# myBox.net
KiCad netlist of a schematic drawn in EAGLE
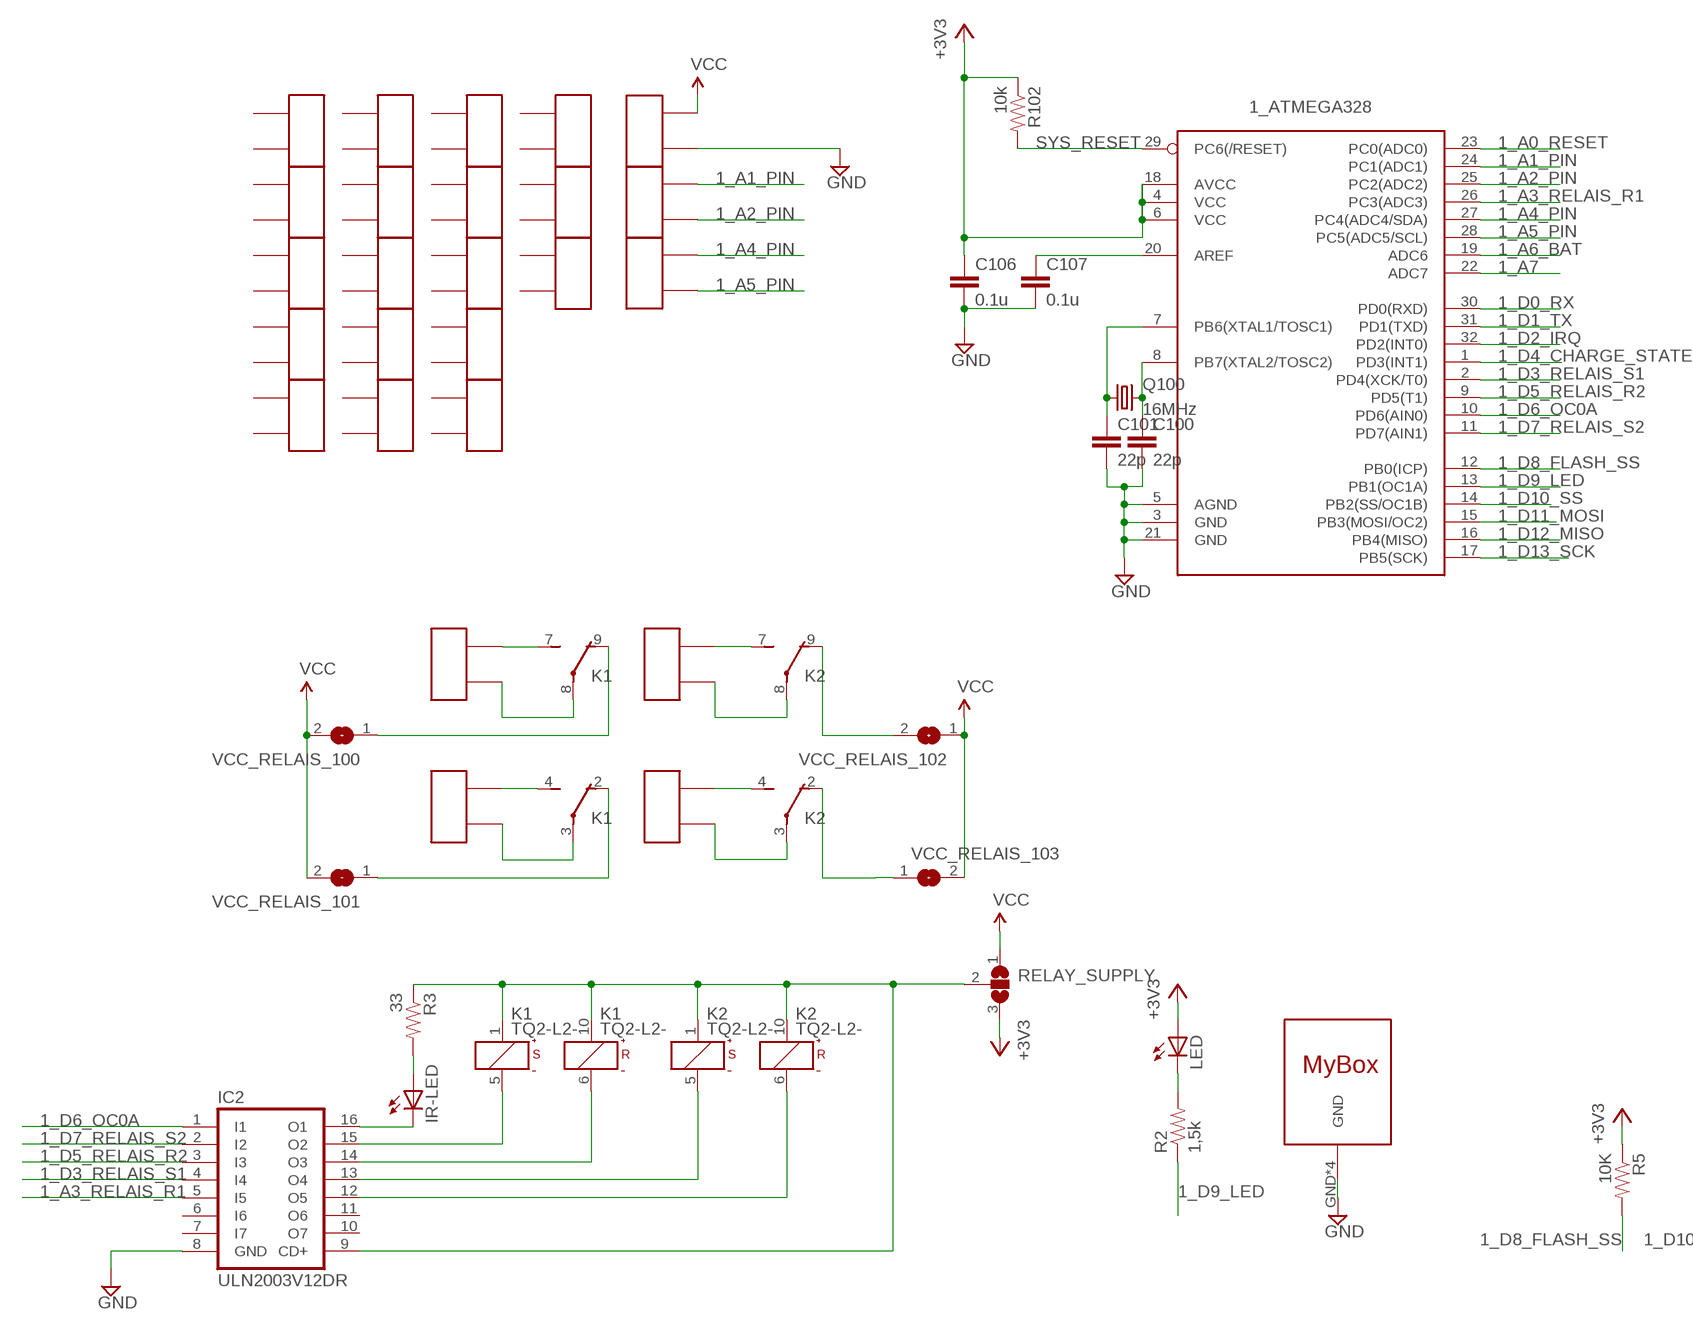
[diagram p0: schematic, sheet 1, part 1 of 2]
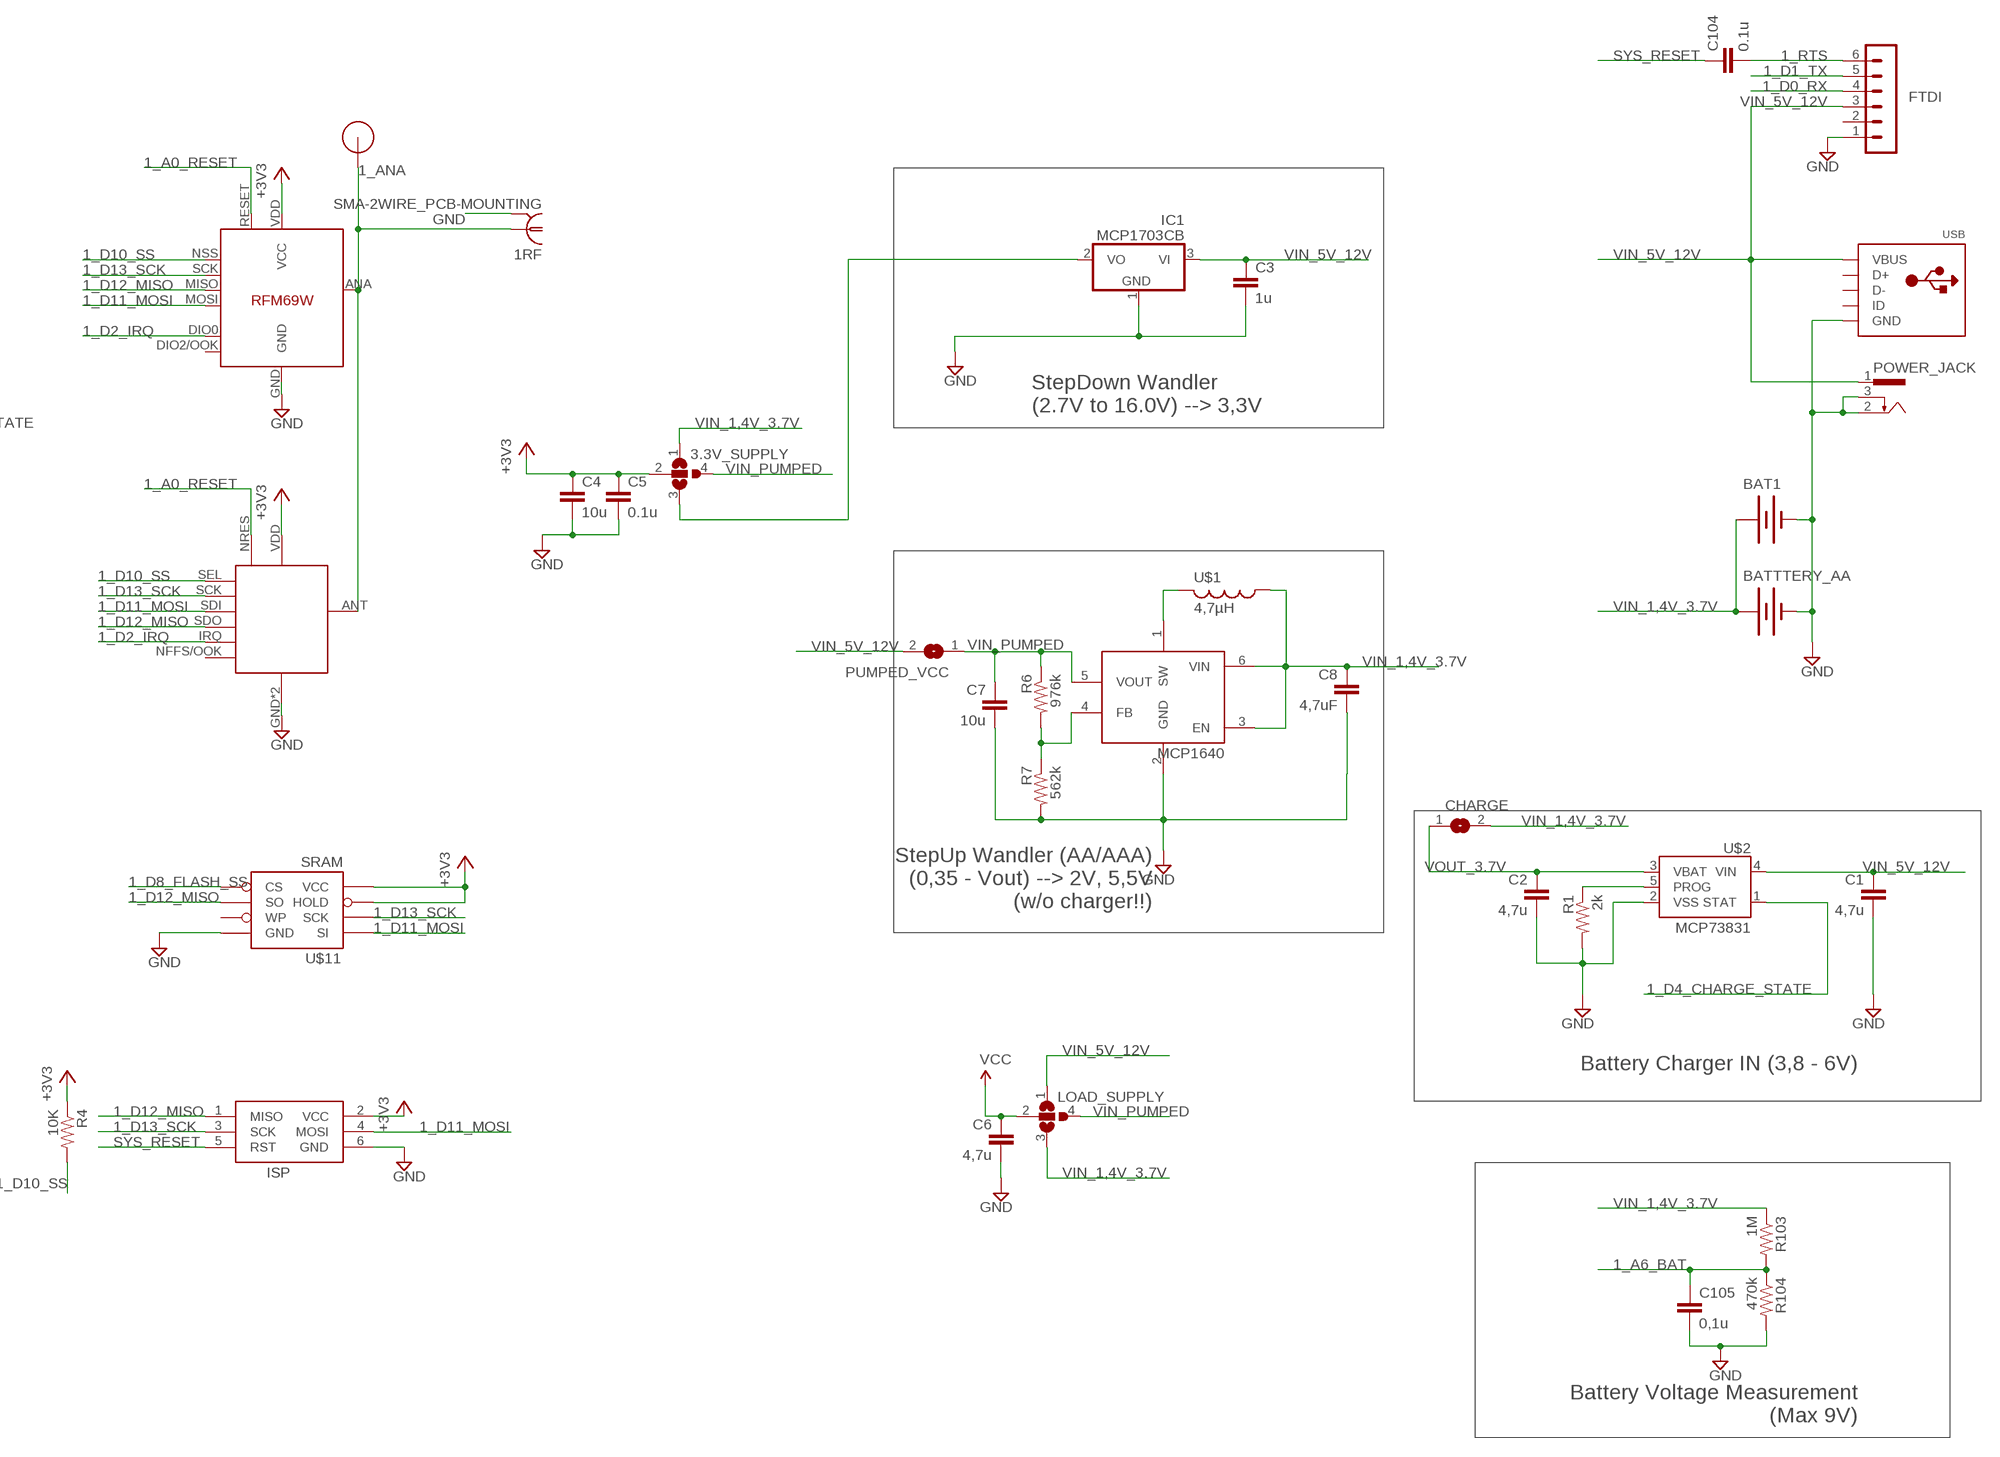
[diagram p1: schematic, sheet 1, part 2 of 2]

(export (version "E")
  (design (tool "Eeschema 10.0.6"))
  (components
    (comp (ref "1RF")
      (value "SMA-2WIRE_PCB-MOUNTING")
      (footprint "eagle-import:J01151A0931")
      (libsource (lib "eagle-import") (part "SMA-2WIRE_PCB-MOUNTING"))
    )
    (comp (ref "1_ATMEGA328")
      (value "ATMega-328")
      (footprint "eagle-import:TQFP32-08")
      (libsource (lib "eagle-import") (part "ATMEGA168/328TQFP32"))
    )
    (comp (ref "1_RFM12")
      (value "RFM12B_MINPADS")
      (footprint "eagle-import:RFM12B-MINPADS")
      (libsource (lib "eagle-import") (part "RFM12B_MINPADS"))
    )
    (comp (ref "1_RFM69")
      (value "RFM69_MINIPADS")
      (footprint "eagle-import:RFM69W-MINPADS")
      (libsource (lib "eagle-import") (part "RFM69_MINIPADS"))
    )
    (comp (ref "3.3V_SUPPLY")
      (value "SJ3W")
      (footprint "eagle-import:SJ_3")
      (libsource (lib "eagle-import") (part "SJ3W"))
    )
    (comp (ref "ADC1")
      (value "HDR_2PIN")
      (footprint "eagle-import:1X02_NS")
      (libsource (lib "eagle-import") (part "HDR_2PIN"))
    )
    (comp (ref "ADC2")
      (value "HDR_2PIN")
      (footprint "eagle-import:1X02_NS")
      (libsource (lib "eagle-import") (part "HDR_2PIN"))
    )
    (comp (ref "BAT1")
      (value "BATTERY")
      (footprint "eagle-import:BATTERY-CR2")
      (libsource (lib "eagle-import") (part "BATTERY"))
    )
    (comp (ref "BATTTERY_AA")
      (value "BATTERYAA")
      (footprint "eagle-import:BATTERY-AA")
      (libsource (lib "eagle-import") (part "BATTERYAA"))
    )
    (comp (ref "C1")
      (value "4,7u")
      (footprint "eagle-import:0603-CAP")
      (libsource (lib "eagle-import") (part "CAP0603-CAP"))
    )
    (comp (ref "C2")
      (value "4,7u")
      (footprint "eagle-import:0603-CAP")
      (libsource (lib "eagle-import") (part "CAP0603-CAP"))
    )
    (comp (ref "C3")
      (value "1u")
      (footprint "eagle-import:0603-CAP")
      (libsource (lib "eagle-import") (part "CAP0603-CAP"))
    )
    (comp (ref "C4")
      (value "10u")
      (footprint "eagle-import:0603-CAP")
      (libsource (lib "eagle-import") (part "CAP0603-CAP"))
    )
    (comp (ref "C5")
      (value "0.1u")
      (footprint "eagle-import:0603-CAP")
      (libsource (lib "eagle-import") (part "CAP0603-CAP"))
    )
    (comp (ref "C6")
      (value "4,7u")
      (footprint "eagle-import:0603-CAP")
      (libsource (lib "eagle-import") (part "CAP0603-CAP"))
    )
    (comp (ref "C7")
      (value "10u")
      (footprint "eagle-import:0603-CAP")
      (libsource (lib "eagle-import") (part "CAP0603-CAP"))
    )
    (comp (ref "C8")
      (value "4,7uF")
      (footprint "eagle-import:0603-CAP")
      (libsource (lib "eagle-import") (part "CAP0603-CAP"))
    )
    (comp (ref "C100")
      (value "22p")
      (footprint "eagle-import:0603-CAP")
      (libsource (lib "eagle-import") (part "CAP0603-CAP"))
    )
    (comp (ref "C101")
      (value "22p")
      (footprint "eagle-import:0603-CAP")
      (libsource (lib "eagle-import") (part "CAP0603-CAP"))
    )
    (comp (ref "C104")
      (value "0.1u")
      (footprint "eagle-import:0603-CAP")
      (libsource (lib "eagle-import") (part "CAP0603-CAP"))
    )
    (comp (ref "C105")
      (value "0,1u")
      (footprint "eagle-import:0603-CAP")
      (libsource (lib "eagle-import") (part "CAP0603-CAP"))
    )
    (comp (ref "C106")
      (value "0.1u")
      (footprint "eagle-import:0603-CAP")
      (libsource (lib "eagle-import") (part "CAP0603-CAP"))
    )
    (comp (ref "C107")
      (value "0.1u")
      (footprint "eagle-import:0603-CAP")
      (libsource (lib "eagle-import") (part "CAP0603-CAP"))
    )
    (comp (ref "CHARGE")
      (value "SJ")
      (footprint "eagle-import:SJ")
      (libsource (lib "eagle-import") (part "SJ"))
    )
    (comp (ref "FTDI")
      (value "FTDI")
      (footprint "eagle-import:MA06-1")
      (libsource (lib "eagle-import") (part "MA06-1"))
    )
    (comp (ref "IC1")
      (value "MCP1703CB")
      (footprint "eagle-import:SOT23")
      (libsource (lib "eagle-import") (part "MCP1703CB"))
    )
    (comp (ref "IC2")
      (value "ULN2003V12DR")
      (footprint "eagle-import:SO16")
      (libsource (lib "eagle-import") (part "ULN2003AD"))
    )
    (comp (ref "IR-LED")
      (value "LED5MM")
      (footprint "eagle-import:LED5MM")
      (libsource (lib "eagle-import") (part "led_LED5MM"))
    )
    (comp (ref "IR/RELAY_SATELLITE")
      (value "MY-BOX")
      (footprint "eagle-import:MY-BOX")
      (libsource (lib "eagle-import") (part "MY-BOX"))
    )
    (comp (ref "ISP")
      (value "AVRISP")
      (footprint "eagle-import:AVRISP-EDGE")
      (fields (field (name "BUERKLIN") "56F6228"))
      (libsource (lib "eagle-import") (part "AVRISP"))
    )
    (comp (ref "K1")
      (value "TQ2-L2-")
      (footprint "eagle-import:TQ2")
      (fields
        (field (name "MF") "AROMAT/ MATSUSHITA")
        (field (name "MPN") "TQ2-L2-9V")
        (field (name "BUERKLIN") "30 G 7570")
        (field (name "MPN_1") "TQ2-L2-3V")
      )
      (libsource (lib "eagle-import") (part "TQ2?-L2-"))
    )
    (comp (ref "K2")
      (value "TQ2-L2-")
      (footprint "eagle-import:TQ2")
      (fields
        (field (name "MF") "AROMAT/ MATSUSHITA")
        (field (name "MPN") "TQ2-L2-9V")
        (field (name "BUERKLIN") "30 G 7570")
        (field (name "MPN_1") "TQ2-L2-3V")
      )
      (libsource (lib "eagle-import") (part "TQ2?-L2-"))
    )
    (comp (ref "LED")
      (value "LED3MM")
      (footprint "eagle-import:LED3MM")
      (libsource (lib "eagle-import") (part "LED3MM"))
    )
    (comp (ref "LOAD_SUPPLY")
      (value "SJ3W")
      (footprint "eagle-import:SJ_3")
      (libsource (lib "eagle-import") (part "SJ3W"))
    )
    (comp (ref "POWER_JACK")
      (value "LUMBERG_1613-200-62")
      (footprint "eagle-import:733980-62")
      (libsource (lib "eagle-import") (part "LUMBERG_1613-200-62"))
    )
    (comp (ref "PUMPED_VCC")
      (value "SJ")
      (footprint "eagle-import:SJ")
      (libsource (lib "eagle-import") (part "SJ"))
    )
    (comp (ref "Q100")
      (value "16MHz")
      (footprint "eagle-import:HC49_S")
      (libsource (lib "eagle-import") (part "CRYSTALHC49S"))
    )
    (comp (ref "R1")
      (value "2k")
      (footprint "eagle-import:0603-RES")
      (libsource (lib "eagle-import") (part "RESISTOR0603-RES"))
    )
    (comp (ref "R2")
      (value "1,5k")
      (footprint "eagle-import:0603-RES")
      (libsource (lib "eagle-import") (part "RESISTOR0603-RES"))
    )
    (comp (ref "R3")
      (value "33")
      (footprint "eagle-import:0603-RES")
      (libsource (lib "eagle-import") (part "RESISTOR0603-RES"))
    )
    (comp (ref "R4")
      (value "10K")
      (footprint "eagle-import:0603-RES")
      (libsource (lib "eagle-import") (part "RESISTOR0603-RES"))
    )
    (comp (ref "R5")
      (value "10K")
      (footprint "eagle-import:0603-RES")
      (libsource (lib "eagle-import") (part "RESISTOR0603-RES"))
    )
    (comp (ref "R6")
      (value "976k")
      (footprint "eagle-import:0603-RES")
      (libsource (lib "eagle-import") (part "RESISTOR0603-RES"))
    )
    (comp (ref "R7")
      (value "562k")
      (footprint "eagle-import:0603-RES")
      (libsource (lib "eagle-import") (part "RESISTOR0603-RES"))
    )
    (comp (ref "R102")
      (value "10k")
      (footprint "eagle-import:0603-RES")
      (libsource (lib "eagle-import") (part "RESISTOR0603-RES"))
    )
    (comp (ref "R103")
      (value "1M")
      (footprint "eagle-import:0603-RES")
      (libsource (lib "eagle-import") (part "RESISTOR0603-RES"))
    )
    (comp (ref "R104")
      (value "470k")
      (footprint "eagle-import:0603-RES")
      (libsource (lib "eagle-import") (part "RESISTOR0603-RES"))
    )
    (comp (ref "RELAY_SUPPLY")
      (value "SJ2W")
      (footprint "eagle-import:SJ_2")
      (libsource (lib "eagle-import") (part "SJ2W"))
    )
    (comp (ref "U$1")
      (value "4,7µH")
      (footprint "eagle-import:INDUCTOR_EPCOS")
      (libsource (lib "eagle-import") (part "INDUCTOR_B82462G"))
    )
    (comp (ref "U$2")
      (value "MCP73831")
      (footprint "eagle-import:SOT23-5")
      (libsource (lib "eagle-import") (part "MCP73831"))
    )
    (comp (ref "U$3")
      (value "HDR_2PIN")
      (footprint "eagle-import:1X02_NS")
      (libsource (lib "eagle-import") (part "HDR_2PIN"))
    )
    (comp (ref "U$4")
      (value "HDR_2PIN")
      (footprint "eagle-import:1X02_NS")
      (libsource (lib "eagle-import") (part "HDR_2PIN"))
    )
    (comp (ref "U$5")
      (value "HDR_2PIN")
      (footprint "eagle-import:1X02_NS")
      (libsource (lib "eagle-import") (part "HDR_2PIN"))
    )
    (comp (ref "U$6")
      (value "HDR_2PIN")
      (footprint "eagle-import:1X02_NS")
      (libsource (lib "eagle-import") (part "HDR_2PIN"))
    )
    (comp (ref "U$7")
      (value "HDR_2PIN")
      (footprint "eagle-import:1X02_NS")
      (libsource (lib "eagle-import") (part "HDR_2PIN"))
    )
    (comp (ref "U$8")
      (value "HDR_2PIN")
      (footprint "eagle-import:1X02_NS")
      (libsource (lib "eagle-import") (part "HDR_2PIN"))
    )
    (comp (ref "U$9")
      (value "HDR_2PIN")
      (footprint "eagle-import:1X02_NS")
      (libsource (lib "eagle-import") (part "HDR_2PIN"))
    )
    (comp (ref "U$10")
      (value "HDR_2PIN")
      (footprint "eagle-import:1X02_NS")
      (libsource (lib "eagle-import") (part "HDR_2PIN"))
    )
    (comp (ref "U$11")
      (value "SRAM")
      (footprint "eagle-import:LOWPOWERLAB_SO08")
      (libsource (lib "eagle-import") (part "SRAM_32K256JEDEC_3.9MM"))
    )
    (comp (ref "U$12")
      (value "HDR_2PIN")
      (footprint "eagle-import:1X02_NS")
      (libsource (lib "eagle-import") (part "HDR_2PIN"))
    )
    (comp (ref "U$13")
      (value "HDR_2PIN")
      (footprint "eagle-import:1X02_NS")
      (libsource (lib "eagle-import") (part "HDR_2PIN"))
    )
    (comp (ref "U$14")
      (value "HDR_2PIN")
      (footprint "eagle-import:1X02_NS")
      (libsource (lib "eagle-import") (part "HDR_2PIN"))
    )
    (comp (ref "U$15")
      (value "HDR_2PIN")
      (footprint "eagle-import:1X02_NS")
      (libsource (lib "eagle-import") (part "HDR_2PIN"))
    )
    (comp (ref "U$16")
      (value "HDR_2PIN")
      (footprint "eagle-import:1X02_NS")
      (libsource (lib "eagle-import") (part "HDR_2PIN"))
    )
    (comp (ref "U$17")
      (value "HDR_2PIN")
      (footprint "eagle-import:1X02_NS")
      (libsource (lib "eagle-import") (part "HDR_2PIN"))
    )
    (comp (ref "U$18")
      (value "RFM12B_ANTENNA")
      (footprint "eagle-import:RFM12B-ANTENNA")
      (libsource (lib "eagle-import") (part "RFM12B_ANTENNA"))
    )
    (comp (ref "U$19")
      (value "HDR_2PIN")
      (footprint "eagle-import:1X02_NS")
      (libsource (lib "eagle-import") (part "HDR_2PIN"))
    )
    (comp (ref "U$20")
      (value "HDR_2PIN")
      (footprint "eagle-import:1X02_NS")
      (libsource (lib "eagle-import") (part "HDR_2PIN"))
    )
    (comp (ref "U$21")
      (value "HDR_2PIN")
      (footprint "eagle-import:1X02_NS")
      (libsource (lib "eagle-import") (part "HDR_2PIN"))
    )
    (comp (ref "U$22")
      (value "HDR_2PIN")
      (footprint "eagle-import:1X02_NS")
      (libsource (lib "eagle-import") (part "HDR_2PIN"))
    )
    (comp (ref "U$23")
      (value "HDR_2PIN")
      (footprint "eagle-import:1X02_NS")
      (libsource (lib "eagle-import") (part "HDR_2PIN"))
    )
    (comp (ref "U$24")
      (value "HDR_2PIN")
      (footprint "eagle-import:1X02_NS")
      (libsource (lib "eagle-import") (part "HDR_2PIN"))
    )
    (comp (ref "U$25")
      (value "HDR_2PIN")
      (footprint "eagle-import:1X02_NS")
      (libsource (lib "eagle-import") (part "HDR_2PIN"))
    )
    (comp (ref "U$26")
      (value "HDR_2PIN")
      (footprint "eagle-import:1X02_NS")
      (libsource (lib "eagle-import") (part "HDR_2PIN"))
    )
    (comp (ref "U1")
      (value "MCP1640")
      (footprint "eagle-import:SOT23-6")
      (libsource (lib "eagle-import") (part "MCP1640"))
    )
    (comp (ref "USB")
      (value "USBMINIB")
      (footprint "eagle-import:USB-MINIB")
      (libsource (lib "eagle-import") (part "USBMINIB"))
    )
    (comp (ref "VCC")
      (value "HDR_2PIN")
      (footprint "eagle-import:1X02_NS")
      (libsource (lib "eagle-import") (part "HDR_2PIN"))
    )
    (comp (ref "VCC_RELAIS_100")
      (value "SJ")
      (footprint "eagle-import:SJ")
      (libsource (lib "eagle-import") (part "SJ"))
    )
    (comp (ref "VCC_RELAIS_101")
      (value "SJ")
      (footprint "eagle-import:SJ")
      (libsource (lib "eagle-import") (part "SJ"))
    )
    (comp (ref "VCC_RELAIS_102")
      (value "SJ")
      (footprint "eagle-import:SJ")
      (libsource (lib "eagle-import") (part "SJ"))
    )
    (comp (ref "VCC_RELAIS_103")
      (value "SJ")
      (footprint "eagle-import:SJ")
      (libsource (lib "eagle-import") (part "SJ"))
    )
  )
  (nets
    (net (code "1") (name "+3V3") (class "Default")
      (node (ref "1_ATMEGA328") (pin "18") (pinfunction "AVCC_18") (pintype "bidirectional"))
      (node (ref "1_ATMEGA328") (pin "4") (pinfunction "VCC_4") (pintype "bidirectional"))
      (node (ref "1_ATMEGA328") (pin "6") (pinfunction "VCC_6") (pintype "bidirectional"))
      (node (ref "1_RFM12") (pin "VDD") (pinfunction "VDD_VDD") (pintype "bidirectional"))
      (node (ref "1_RFM69") (pin "VDD") (pinfunction "VCC_VDD") (pintype "power_in"))
      (node (ref "3.3V_SUPPLY") (pin "2") (pinfunction "2_2") (pintype "passive"))
      (node (ref "C106") (pin "1") (pinfunction "1_1") (pintype "passive"))
      (node (ref "C4") (pin "1") (pinfunction "1_1") (pintype "passive"))
      (node (ref "C5") (pin "1") (pinfunction "1_1") (pintype "passive"))
      (node (ref "ISP") (pin "2") (pinfunction "VCC_2") (pintype "power_in"))
      (node (ref "LED") (pin "A") (pinfunction "A_A") (pintype "passive"))
      (node (ref "R102") (pin "1") (pinfunction "1_1") (pintype "passive"))
      (node (ref "R4") (pin "1") (pinfunction "1_1") (pintype "passive"))
      (node (ref "R5") (pin "1") (pinfunction "1_1") (pintype "passive"))
      (node (ref "RELAY_SUPPLY") (pin "3") (pinfunction "3_3") (pintype "passive"))
      (node (ref "U$11") (pin "7_HOLD") (pinfunction "HOLD_7_HOLD") (pintype "bidirectional"))
      (node (ref "U$11") (pin "8_VCC") (pinfunction "VCC_8_VCC") (pintype "bidirectional"))
    )
    (net (code "2") (name "/1_A0_RESET") (class "Default")
      (node (ref "1_ATMEGA328") (pin "23") (pinfunction "PC0(ADC0)_23") (pintype "bidirectional"))
      (node (ref "1_RFM12") (pin "NRES") (pinfunction "NRES_NRES") (pintype "bidirectional"))
      (node (ref "1_RFM69") (pin "RESET") (pinfunction "RESET_RESET") (pintype "input"))
    )
    (net (code "3") (name "/1_A1_PIN") (class "Default")
      (node (ref "1_ATMEGA328") (pin "24") (pinfunction "PC1(ADC1)_24") (pintype "bidirectional"))
      (node (ref "ADC1") (pin "1") (pinfunction "P$1_1") (pintype "bidirectional"))
    )
    (net (code "4") (name "/1_A2_PIN") (class "Default")
      (node (ref "1_ATMEGA328") (pin "25") (pinfunction "PC2(ADC2)_25") (pintype "bidirectional"))
      (node (ref "ADC1") (pin "2") (pinfunction "P$2_2") (pintype "bidirectional"))
    )
    (net (code "5") (name "/1_A3_RELAIS_R1") (class "Default")
      (node (ref "1_ATMEGA328") (pin "26") (pinfunction "PC3(ADC3)_26") (pintype "bidirectional"))
      (node (ref "IC2") (pin "5") (pinfunction "I5_5") (pintype "input"))
    )
    (net (code "6") (name "/1_A4_PIN") (class "Default")
      (node (ref "1_ATMEGA328") (pin "27") (pinfunction "PC4(ADC4/SDA)_27") (pintype "bidirectional"))
      (node (ref "ADC2") (pin "1") (pinfunction "P$1_1") (pintype "bidirectional"))
    )
    (net (code "7") (name "/1_A5_PIN") (class "Default")
      (node (ref "1_ATMEGA328") (pin "28") (pinfunction "PC5(ADC5/SCL)_28") (pintype "bidirectional"))
      (node (ref "ADC2") (pin "2") (pinfunction "P$2_2") (pintype "bidirectional"))
    )
    (net (code "8") (name "/1_A6_BAT") (class "Default")
      (node (ref "1_ATMEGA328") (pin "19") (pinfunction "ADC6_19") (pintype "bidirectional"))
      (node (ref "C105") (pin "1") (pinfunction "1_1") (pintype "passive"))
      (node (ref "R103") (pin "2") (pinfunction "2_2") (pintype "passive"))
      (node (ref "R104") (pin "1") (pinfunction "1_1") (pintype "passive"))
    )
    (net (code "9") (name "/1_A7") (class "Default")
      (node (ref "1_ATMEGA328") (pin "22") (pinfunction "ADC7_22") (pintype "bidirectional"))
    )
    (net (code "10") (name "/1_ANA") (class "Default")
      (node (ref "1RF") (pin "1") (pinfunction "1_1") (pintype "passive"))
      (node (ref "1_RFM12") (pin "ANT") (pinfunction "ANT_ANT") (pintype "bidirectional"))
      (node (ref "1_RFM69") (pin "ANA") (pinfunction "ANT_ANA") (pintype "passive"))
      (node (ref "U$18") (pin "P$1") (pinfunction "1_P$1") (pintype "bidirectional"))
    )
    (net (code "11") (name "/1_D0_RX") (class "Default")
      (node (ref "1_ATMEGA328") (pin "30") (pinfunction "PD0(RXD)_30") (pintype "bidirectional"))
      (node (ref "FTDI") (pin "4") (pinfunction "4_4") (pintype "passive"))
    )
    (net (code "12") (name "/1_D1_TX") (class "Default")
      (node (ref "1_ATMEGA328") (pin "31") (pinfunction "PD1(TXD)_31") (pintype "bidirectional"))
      (node (ref "FTDI") (pin "5") (pinfunction "5_5") (pintype "passive"))
    )
    (net (code "13") (name "/1_D2_IRQ") (class "Default")
      (node (ref "1_ATMEGA328") (pin "32") (pinfunction "PD2(INT0)_32") (pintype "bidirectional"))
      (node (ref "1_RFM12") (pin "IRQ") (pinfunction "IRQ_IRQ") (pintype "bidirectional"))
      (node (ref "1_RFM69") (pin "DIO0") (pinfunction "DIO0/IRQ_DIO0") (pintype "open_collector"))
    )
    (net (code "14") (name "/1_D3_RELAIS_S1") (class "Default")
      (node (ref "1_ATMEGA328") (pin "2") (pinfunction "PD4(XCK/T0)_2") (pintype "bidirectional"))
      (node (ref "IC2") (pin "4") (pinfunction "I4_4") (pintype "input"))
    )
    (net (code "15") (name "/1_D4_CHARGE_STATE") (class "Default")
      (node (ref "1_ATMEGA328") (pin "1") (pinfunction "PD3(INT1)_1") (pintype "bidirectional"))
      (node (ref "U$2") (pin "1") (pinfunction "STAT_1") (pintype "output"))
    )
    (net (code "16") (name "/1_D5_RELAIS_R2") (class "Default")
      (node (ref "1_ATMEGA328") (pin "9") (pinfunction "PD5(T1)_9") (pintype "bidirectional"))
      (node (ref "IC2") (pin "3") (pinfunction "I3_3") (pintype "input"))
    )
    (net (code "17") (name "/1_D6_OC0A") (class "Default")
      (node (ref "1_ATMEGA328") (pin "10") (pinfunction "PD6(AIN0)_10") (pintype "bidirectional"))
      (node (ref "IC2") (pin "1") (pinfunction "I1_1") (pintype "input"))
    )
    (net (code "18") (name "/1_D7_RELAIS_S2") (class "Default")
      (node (ref "1_ATMEGA328") (pin "11") (pinfunction "PD7(AIN1)_11") (pintype "bidirectional"))
      (node (ref "IC2") (pin "2") (pinfunction "I2_2") (pintype "input"))
    )
    (net (code "19") (name "/1_D8_FLASH_SS") (class "Default")
      (node (ref "1_ATMEGA328") (pin "12") (pinfunction "PB0(ICP)_12") (pintype "bidirectional"))
      (node (ref "R5") (pin "2") (pinfunction "2_2") (pintype "passive"))
      (node (ref "U$11") (pin "1_CS") (pinfunction "CS_1_CS") (pintype "bidirectional"))
    )
    (net (code "20") (name "/1_D9_LED") (class "Default")
      (node (ref "1_ATMEGA328") (pin "13") (pinfunction "PB1(OC1A)_13") (pintype "bidirectional"))
      (node (ref "R2") (pin "1") (pinfunction "1_1") (pintype "passive"))
    )
    (net (code "21") (name "/1_D10_SS") (class "Default")
      (node (ref "1_ATMEGA328") (pin "14") (pinfunction "PB2(SS/OC1B)_14") (pintype "bidirectional"))
      (node (ref "1_RFM12") (pin "SEL") (pinfunction "SEL_SEL") (pintype "bidirectional"))
      (node (ref "1_RFM69") (pin "NSS") (pinfunction "SEL_NSS") (pintype "input"))
      (node (ref "R4") (pin "2") (pinfunction "2_2") (pintype "passive"))
    )
    (net (code "22") (name "/1_D11_MOSI") (class "Default")
      (node (ref "1_ATMEGA328") (pin "15") (pinfunction "PB3(MOSI/OC2)_15") (pintype "bidirectional"))
      (node (ref "1_RFM12") (pin "SDI") (pinfunction "SDI/MOSI_SDI") (pintype "bidirectional"))
      (node (ref "1_RFM69") (pin "MOSI") (pinfunction "MOSI_MOSI") (pintype "output"))
      (node (ref "ISP") (pin "4") (pinfunction "MOSI_4") (pintype "output"))
      (node (ref "U$11") (pin "5_SI") (pinfunction "SI_5_SI") (pintype "bidirectional"))
    )
    (net (code "23") (name "/1_D12_MISO") (class "Default")
      (node (ref "1_ATMEGA328") (pin "16") (pinfunction "PB4(MISO)_16") (pintype "bidirectional"))
      (node (ref "1_RFM12") (pin "SDO") (pinfunction "SDO/MISO_SDO") (pintype "bidirectional"))
      (node (ref "1_RFM69") (pin "MISO") (pinfunction "MISO_MISO") (pintype "input"))
      (node (ref "ISP") (pin "1") (pinfunction "MISO_1") (pintype "input"))
      (node (ref "U$11") (pin "2_SO") (pinfunction "SO_2_SO") (pintype "bidirectional"))
    )
    (net (code "24") (name "/1_D13_SCK") (class "Default")
      (node (ref "1_ATMEGA328") (pin "17") (pinfunction "PB5(SCK)_17") (pintype "bidirectional"))
      (node (ref "1_RFM12") (pin "SCK") (pinfunction "SCK_SCK") (pintype "bidirectional"))
      (node (ref "1_RFM69") (pin "SCK") (pinfunction "SCK_SCK") (pintype "input"))
      (node (ref "ISP") (pin "3") (pinfunction "SCK_3") (pintype "output"))
      (node (ref "U$11") (pin "6_SCK") (pinfunction "SCK_6_SCK") (pintype "bidirectional"))
    )
    (net (code "25") (name "/1_RTS") (class "Default")
      (node (ref "C104") (pin "2") (pinfunction "2_2") (pintype "passive"))
      (node (ref "FTDI") (pin "6") (pinfunction "6_6") (pintype "passive"))
    )
    (net (code "26") (name "/SYS_RESET") (class "Default")
      (node (ref "1_ATMEGA328") (pin "29") (pinfunction "PC6(/RESET)_29") (pintype "bidirectional"))
      (node (ref "C104") (pin "1") (pinfunction "1_1") (pintype "passive"))
      (node (ref "ISP") (pin "5") (pinfunction "RST_5") (pintype "output"))
      (node (ref "R102") (pin "2") (pinfunction "2_2") (pintype "passive"))
    )
    (net (code "27") (name "/VIN_1,4V_3.7V") (class "Default")
      (node (ref "3.3V_SUPPLY") (pin "1") (pinfunction "1_1") (pintype "passive"))
      (node (ref "BAT1") (pin "PWR@1") (pinfunction "+_PWR@1") (pintype "power_in"))
      (node (ref "BATTTERY_AA") (pin "PWR@1") (pinfunction "+_PWR@1") (pintype "power_in"))
      (node (ref "C8") (pin "1") (pinfunction "1_1") (pintype "passive"))
      (node (ref "CHARGE") (pin "2") (pinfunction "2_2") (pintype "passive"))
      (node (ref "LOAD_SUPPLY") (pin "3") (pinfunction "3_3") (pintype "passive"))
      (node (ref "R103") (pin "1") (pinfunction "1_1") (pintype "passive"))
      (node (ref "U$1") (pin "P$1") (pinfunction "1_P$1") (pintype "passive"))
      (node (ref "U1") (pin "3") (pinfunction "EN_3") (pintype "input"))
      (node (ref "U1") (pin "6") (pinfunction "VIN_6") (pintype "input"))
    )
    (net (code "28") (name "/VIN_5V_12V") (class "Default")
      (node (ref "C1") (pin "1") (pinfunction "1_1") (pintype "passive"))
      (node (ref "C3") (pin "1") (pinfunction "1_1") (pintype "passive"))
      (node (ref "FTDI") (pin "3") (pinfunction "3_3") (pintype "passive"))
      (node (ref "IC1") (pin "3") (pinfunction "VI_3") (pintype "input"))
      (node (ref "LOAD_SUPPLY") (pin "1") (pinfunction "1_1") (pintype "passive"))
      (node (ref "POWER_JACK") (pin "1") (pinfunction "1_1") (pintype "passive"))
      (node (ref "PUMPED_VCC") (pin "2") (pinfunction "2_2") (pintype "passive"))
      (node (ref "U$2") (pin "4") (pinfunction "VIN_4") (pintype "power_in"))
      (node (ref "USB") (pin "VBUS") (pinfunction "VBUS_VBUS") (pintype "power_in"))
    )
    (net (code "29") (name "/VIN_PUMPED") (class "Default")
      (node (ref "3.3V_SUPPLY") (pin "4") (pinfunction "4_4") (pintype "passive"))
      (node (ref "C7") (pin "1") (pinfunction "1_1") (pintype "passive"))
      (node (ref "LOAD_SUPPLY") (pin "4") (pinfunction "4_4") (pintype "passive"))
      (node (ref "PUMPED_VCC") (pin "1") (pinfunction "1_1") (pintype "passive"))
      (node (ref "R6") (pin "1") (pinfunction "1_1") (pintype "passive"))
      (node (ref "U1") (pin "5") (pinfunction "VOUT_5") (pintype "output"))
    )
    (net (code "30") (name "/VOUT_3.7V") (class "Default")
      (node (ref "C2") (pin "1") (pinfunction "1_1") (pintype "passive"))
      (node (ref "CHARGE") (pin "1") (pinfunction "1_1") (pintype "passive"))
      (node (ref "U$2") (pin "3") (pinfunction "VBAT_3") (pintype "power_in"))
    )
    (net (code "31") (name "GND") (class "Default")
      (node (ref "1RF") (pin "G@1") (pinfunction "2_G@1") (pintype "passive"))
      (node (ref "1RF") (pin "G@2") (pinfunction "2_G@2") (pintype "passive"))
      (node (ref "1RF") (pin "G@3") (pinfunction "2_G@3") (pintype "passive"))
      (node (ref "1RF") (pin "G@4") (pinfunction "2_G@4") (pintype "passive"))
      (node (ref "1_ATMEGA328") (pin "21") (pinfunction "GND_21") (pintype "bidirectional"))
      (node (ref "1_ATMEGA328") (pin "3") (pinfunction "GND_3") (pintype "bidirectional"))
      (node (ref "1_ATMEGA328") (pin "5") (pinfunction "AGND_5") (pintype "bidirectional"))
      (node (ref "1_RFM12") (pin "GND") (pinfunction "GND_GND") (pintype "bidirectional"))
      (node (ref "1_RFM12") (pin "GND1") (pinfunction "GND_GND1") (pintype "bidirectional"))
      (node (ref "1_RFM69") (pin "GND") (pinfunction "GND_GND") (pintype "power_in"))
      (node (ref "BAT1") (pin "GND@1") (pinfunction "-_GND@1") (pintype "power_in"))
      (node (ref "BATTTERY_AA") (pin "GND@1") (pinfunction "-_GND@1") (pintype "power_in"))
      (node (ref "C1") (pin "2") (pinfunction "2_2") (pintype "passive"))
      (node (ref "C100") (pin "2") (pinfunction "2_2") (pintype "passive"))
      (node (ref "C101") (pin "2") (pinfunction "2_2") (pintype "passive"))
      (node (ref "C105") (pin "2") (pinfunction "2_2") (pintype "passive"))
      (node (ref "C106") (pin "2") (pinfunction "2_2") (pintype "passive"))
      (node (ref "C107") (pin "2") (pinfunction "2_2") (pintype "passive"))
      (node (ref "C2") (pin "2") (pinfunction "2_2") (pintype "passive"))
      (node (ref "C3") (pin "2") (pinfunction "2_2") (pintype "passive"))
      (node (ref "C4") (pin "2") (pinfunction "2_2") (pintype "passive"))
      (node (ref "C5") (pin "2") (pinfunction "2_2") (pintype "passive"))
      (node (ref "C6") (pin "2") (pinfunction "2_2") (pintype "passive"))
      (node (ref "C7") (pin "2") (pinfunction "2_2") (pintype "passive"))
      (node (ref "C8") (pin "2") (pinfunction "2_2") (pintype "passive"))
      (node (ref "FTDI") (pin "1") (pinfunction "1_1") (pintype "passive"))
      (node (ref "IC1") (pin "1") (pinfunction "GND_1") (pintype "passive"))
      (node (ref "IC2") (pin "8") (pinfunction "GND_8") (pintype "power_in"))
      (node (ref "IR/RELAY_SATELLITE") (pin "GND") (pinfunction "GND_GND") (pintype "bidirectional"))
      (node (ref "IR/RELAY_SATELLITE") (pin "GND1") (pinfunction "GND_GND1") (pintype "bidirectional"))
      (node (ref "IR/RELAY_SATELLITE") (pin "GND2") (pinfunction "GND_GND2") (pintype "bidirectional"))
      (node (ref "IR/RELAY_SATELLITE") (pin "GND3") (pinfunction "GND_GND3") (pintype "bidirectional"))
      (node (ref "ISP") (pin "6") (pinfunction "GND_6") (pintype "power_in"))
      (node (ref "POWER_JACK") (pin "2") (pinfunction "2_2") (pintype "passive"))
      (node (ref "POWER_JACK") (pin "3") (pinfunction "3_3") (pintype "passive"))
      (node (ref "R1") (pin "2") (pinfunction "2_2") (pintype "passive"))
      (node (ref "R104") (pin "2") (pinfunction "2_2") (pintype "passive"))
      (node (ref "R7") (pin "2") (pinfunction "2_2") (pintype "passive"))
      (node (ref "U$11") (pin "4_GND") (pinfunction "GND_4_GND") (pintype "bidirectional"))
      (node (ref "U$2") (pin "2") (pinfunction "VSS_2") (pintype "power_in"))
      (node (ref "U1") (pin "2") (pinfunction "GND_2") (pintype "power_in"))
      (node (ref "USB") (pin "GND") (pinfunction "GND_GND") (pintype "power_in"))
      (node (ref "VCC") (pin "2") (pinfunction "P$2_2") (pintype "bidirectional"))
    )
    (net (code "32") (name "Net-(1_ATMEGA328-AREF)") (class "Default")
      (node (ref "1_ATMEGA328") (pin "20") (pinfunction "AREF_20") (pintype "bidirectional"))
      (node (ref "C107") (pin "1") (pinfunction "1_1") (pintype "passive"))
    )
    (net (code "33") (name "Net-(1_ATMEGA328-PB6(XTAL1{slash}TOSC1))") (class "Default")
      (node (ref "1_ATMEGA328") (pin "7") (pinfunction "PB6(XTAL1/TOSC1)_7") (pintype "bidirectional"))
      (node (ref "C101") (pin "1") (pinfunction "1_1") (pintype "passive"))
      (node (ref "Q100") (pin "1") (pinfunction "1_1") (pintype "passive"))
    )
    (net (code "34") (name "Net-(1_ATMEGA328-PB7(XTAL2{slash}TOSC2))") (class "Default")
      (node (ref "1_ATMEGA328") (pin "8") (pinfunction "PB7(XTAL2/TOSC2)_8") (pintype "bidirectional"))
      (node (ref "C100") (pin "1") (pinfunction "1_1") (pintype "passive"))
      (node (ref "Q100") (pin "2") (pinfunction "2_2") (pintype "passive"))
    )
    (net (code "35") (name "Net-(IC1-VO)") (class "Default")
      (node (ref "3.3V_SUPPLY") (pin "3") (pinfunction "3_3") (pintype "passive"))
      (node (ref "IC1") (pin "2") (pinfunction "VO_2") (pintype "passive"))
    )
    (net (code "36") (name "Net-(IC2-CD+)") (class "Default")
      (node (ref "IC2") (pin "9") (pinfunction "CD+_9") (pintype "passive"))
      (node (ref "K1") (pin "1") (pinfunction "+_1") (pintype "passive"))
      (node (ref "K1") (pin "10") (pinfunction "+_10") (pintype "passive"))
      (node (ref "K2") (pin "1") (pinfunction "+_1") (pintype "passive"))
      (node (ref "K2") (pin "10") (pinfunction "+_10") (pintype "passive"))
      (node (ref "R3") (pin "1") (pinfunction "1_1") (pintype "passive"))
      (node (ref "RELAY_SUPPLY") (pin "2") (pinfunction "2_2") (pintype "passive"))
    )
    (net (code "37") (name "Net-(IC2-O1)") (class "Default")
      (node (ref "IC2") (pin "16") (pinfunction "O1_16") (pintype "open_collector"))
      (node (ref "IR-LED") (pin "K") (pinfunction "C_K") (pintype "passive"))
    )
    (net (code "38") (name "Net-(IC2-O2)") (class "Default")
      (node (ref "IC2") (pin "15") (pinfunction "O2_15") (pintype "open_collector"))
      (node (ref "K1") (pin "5") (pinfunction "-_5") (pintype "passive"))
    )
    (net (code "39") (name "Net-(IC2-O3)") (class "Default")
      (node (ref "IC2") (pin "14") (pinfunction "O3_14") (pintype "open_collector"))
      (node (ref "K1") (pin "6") (pinfunction "-_6") (pintype "passive"))
    )
    (net (code "40") (name "Net-(IC2-O4)") (class "Default")
      (node (ref "IC2") (pin "13") (pinfunction "O4_13") (pintype "open_collector"))
      (node (ref "K2") (pin "5") (pinfunction "-_5") (pintype "passive"))
    )
    (net (code "41") (name "Net-(IC2-O5)") (class "Default")
      (node (ref "IC2") (pin "12") (pinfunction "O5_12") (pintype "open_collector"))
      (node (ref "K2") (pin "6") (pinfunction "-_6") (pintype "passive"))
    )
    (net (code "42") (name "Net-(IR-LED-PadA)") (class "Default")
      (node (ref "IR-LED") (pin "A") (pinfunction "A_A") (pintype "passive"))
      (node (ref "R3") (pin "2") (pinfunction "2_2") (pintype "passive"))
    )
    (net (code "43") (name "Net-(K1A-O)") (class "Default")
      (node (ref "K1") (pin "2") (pinfunction "O_2") (pintype "passive"))
      (node (ref "VCC_RELAIS_101") (pin "1") (pinfunction "1_1") (pintype "passive"))
    )
    (net (code "44") (name "Net-(K1A-P)") (class "Default")
      (node (ref "K1") (pin "3") (pinfunction "P_3") (pintype "passive"))
      (node (ref "U$22") (pin "1") (pinfunction "P$1_1") (pintype "bidirectional"))
    )
    (net (code "45") (name "Net-(K1A-S)") (class "Default")
      (node (ref "K1") (pin "4") (pinfunction "S_4") (pintype "passive"))
      (node (ref "U$22") (pin "2") (pinfunction "P$2_2") (pintype "bidirectional"))
    )
    (net (code "46") (name "Net-(K1B-O)") (class "Default")
      (node (ref "K1") (pin "9") (pinfunction "O_9") (pintype "passive"))
      (node (ref "VCC_RELAIS_100") (pin "1") (pinfunction "1_1") (pintype "passive"))
    )
    (net (code "47") (name "Net-(K1B-P)") (class "Default")
      (node (ref "K1") (pin "8") (pinfunction "P_8") (pintype "passive"))
      (node (ref "U$21") (pin "1") (pinfunction "P$1_1") (pintype "bidirectional"))
    )
    (net (code "48") (name "Net-(K1B-S)") (class "Default")
      (node (ref "K1") (pin "7") (pinfunction "S_7") (pintype "passive"))
      (node (ref "U$21") (pin "2") (pinfunction "P$2_2") (pintype "bidirectional"))
    )
    (net (code "49") (name "Net-(K2A-O)") (class "Default")
      (node (ref "K2") (pin "2") (pinfunction "O_2") (pintype "passive"))
      (node (ref "VCC_RELAIS_103") (pin "1") (pinfunction "1_1") (pintype "passive"))
    )
    (net (code "50") (name "Net-(K2A-P)") (class "Default")
      (node (ref "K2") (pin "3") (pinfunction "P_3") (pintype "passive"))
      (node (ref "U$24") (pin "1") (pinfunction "P$1_1") (pintype "bidirectional"))
    )
    (net (code "51") (name "Net-(K2A-S)") (class "Default")
      (node (ref "K2") (pin "4") (pinfunction "S_4") (pintype "passive"))
      (node (ref "U$24") (pin "2") (pinfunction "P$2_2") (pintype "bidirectional"))
    )
    (net (code "52") (name "Net-(K2B-O)") (class "Default")
      (node (ref "K2") (pin "9") (pinfunction "O_9") (pintype "passive"))
      (node (ref "VCC_RELAIS_102") (pin "2") (pinfunction "2_2") (pintype "passive"))
    )
    (net (code "53") (name "Net-(K2B-P)") (class "Default")
      (node (ref "K2") (pin "8") (pinfunction "P_8") (pintype "passive"))
      (node (ref "U$23") (pin "1") (pinfunction "P$1_1") (pintype "bidirectional"))
    )
    (net (code "54") (name "Net-(K2B-S)") (class "Default")
      (node (ref "K2") (pin "7") (pinfunction "S_7") (pintype "passive"))
      (node (ref "U$23") (pin "2") (pinfunction "P$2_2") (pintype "bidirectional"))
    )
    (net (code "55") (name "Net-(LED-C)") (class "Default")
      (node (ref "LED") (pin "K") (pinfunction "C_K") (pintype "passive"))
      (node (ref "R2") (pin "2") (pinfunction "2_2") (pintype "passive"))
    )
    (net (code "56") (name "Net-(U$1-2)") (class "Default")
      (node (ref "U$1") (pin "P$2") (pinfunction "2_P$2") (pintype "passive"))
      (node (ref "U1") (pin "1") (pinfunction "SW_1") (pintype "output"))
    )
    (net (code "57") (name "Net-(U$2-PROG)") (class "Default")
      (node (ref "R1") (pin "1") (pinfunction "1_1") (pintype "passive"))
      (node (ref "U$2") (pin "5") (pinfunction "PROG_5") (pintype "input"))
    )
    (net (code "58") (name "Net-(U1-FB)") (class "Default")
      (node (ref "R6") (pin "2") (pinfunction "2_2") (pintype "passive"))
      (node (ref "R7") (pin "1") (pinfunction "1_1") (pintype "passive"))
      (node (ref "U1") (pin "4") (pinfunction "FB_4") (pintype "input"))
    )
    (net (code "59") (name "VCC") (class "Default")
      (node (ref "C6") (pin "1") (pinfunction "1_1") (pintype "passive"))
      (node (ref "LOAD_SUPPLY") (pin "2") (pinfunction "2_2") (pintype "passive"))
      (node (ref "RELAY_SUPPLY") (pin "1") (pinfunction "1_1") (pintype "passive"))
      (node (ref "VCC") (pin "1") (pinfunction "P$1_1") (pintype "bidirectional"))
      (node (ref "VCC_RELAIS_100") (pin "2") (pinfunction "2_2") (pintype "passive"))
      (node (ref "VCC_RELAIS_101") (pin "2") (pinfunction "2_2") (pintype "passive"))
      (node (ref "VCC_RELAIS_102") (pin "1") (pinfunction "1_1") (pintype "passive"))
      (node (ref "VCC_RELAIS_103") (pin "2") (pinfunction "2_2") (pintype "passive"))
    )
    (net (code "60") (name "unconnected-(1_RFM12-PadNFFS{slash}OOK)") (class "Default")
      (node (ref "1_RFM12") (pin "NFFS/OOK") (pinfunction "NFFS/OOK_NFFS/OOK") (pintype "bidirectional"))
    )
    (net (code "61") (name "unconnected-(1_RFM69-PadDIO2{slash}OOK)") (class "Default")
      (node (ref "1_RFM69") (pin "DIO2/OOK") (pinfunction "DIO2/OOK_DIO2/OOK") (pintype "open_collector"))
    )
    (net (code "62") (name "unconnected-(FTDI-Pad2)") (class "Default")
      (node (ref "FTDI") (pin "2") (pinfunction "2_2") (pintype "passive"))
    )
    (net (code "63") (name "unconnected-(IC2-I6-Pad6)") (class "Default")
      (node (ref "IC2") (pin "6") (pinfunction "I6_6") (pintype "input"))
    )
    (net (code "64") (name "unconnected-(IC2-I7-Pad7)") (class "Default")
      (node (ref "IC2") (pin "7") (pinfunction "I7_7") (pintype "input"))
    )
    (net (code "65") (name "unconnected-(IC2-O6-Pad11)") (class "Default")
      (node (ref "IC2") (pin "11") (pinfunction "O6_11") (pintype "open_collector"))
    )
    (net (code "66") (name "unconnected-(IC2-O7-Pad10)") (class "Default")
      (node (ref "IC2") (pin "10") (pinfunction "O7_10") (pintype "open_collector"))
    )
    (net (code "67") (name "unconnected-(U$3-P$1-Pad1)") (class "Default")
      (node (ref "U$3") (pin "1") (pinfunction "P$1_1") (pintype "bidirectional"))
    )
    (net (code "68") (name "unconnected-(U$3-P$2-Pad2)") (class "Default")
      (node (ref "U$3") (pin "2") (pinfunction "P$2_2") (pintype "bidirectional"))
    )
    (net (code "69") (name "unconnected-(U$4-P$1-Pad1)") (class "Default")
      (node (ref "U$4") (pin "1") (pinfunction "P$1_1") (pintype "bidirectional"))
    )
    (net (code "70") (name "unconnected-(U$4-P$2-Pad2)") (class "Default")
      (node (ref "U$4") (pin "2") (pinfunction "P$2_2") (pintype "bidirectional"))
    )
    (net (code "71") (name "unconnected-(U$5-P$1-Pad1)") (class "Default")
      (node (ref "U$5") (pin "1") (pinfunction "P$1_1") (pintype "bidirectional"))
    )
    (net (code "72") (name "unconnected-(U$5-P$2-Pad2)") (class "Default")
      (node (ref "U$5") (pin "2") (pinfunction "P$2_2") (pintype "bidirectional"))
    )
    (net (code "73") (name "unconnected-(U$6-P$1-Pad1)") (class "Default")
      (node (ref "U$6") (pin "1") (pinfunction "P$1_1") (pintype "bidirectional"))
    )
    (net (code "74") (name "unconnected-(U$6-P$2-Pad2)") (class "Default")
      (node (ref "U$6") (pin "2") (pinfunction "P$2_2") (pintype "bidirectional"))
    )
    (net (code "75") (name "unconnected-(U$7-P$1-Pad1)") (class "Default")
      (node (ref "U$7") (pin "1") (pinfunction "P$1_1") (pintype "bidirectional"))
    )
    (net (code "76") (name "unconnected-(U$7-P$2-Pad2)") (class "Default")
      (node (ref "U$7") (pin "2") (pinfunction "P$2_2") (pintype "bidirectional"))
    )
    (net (code "77") (name "unconnected-(U$8-P$1-Pad1)") (class "Default")
      (node (ref "U$8") (pin "1") (pinfunction "P$1_1") (pintype "bidirectional"))
    )
    (net (code "78") (name "unconnected-(U$8-P$2-Pad2)") (class "Default")
      (node (ref "U$8") (pin "2") (pinfunction "P$2_2") (pintype "bidirectional"))
    )
    (net (code "79") (name "unconnected-(U$9-P$1-Pad1)") (class "Default")
      (node (ref "U$9") (pin "1") (pinfunction "P$1_1") (pintype "bidirectional"))
    )
    (net (code "80") (name "unconnected-(U$9-P$2-Pad2)") (class "Default")
      (node (ref "U$9") (pin "2") (pinfunction "P$2_2") (pintype "bidirectional"))
    )
    (net (code "81") (name "unconnected-(U$10-P$1-Pad1)") (class "Default")
      (node (ref "U$10") (pin "1") (pinfunction "P$1_1") (pintype "bidirectional"))
    )
    (net (code "82") (name "unconnected-(U$10-P$2-Pad2)") (class "Default")
      (node (ref "U$10") (pin "2") (pinfunction "P$2_2") (pintype "bidirectional"))
    )
    (net (code "83") (name "unconnected-(U$11-WP-Pad3_WP)") (class "Default")
      (node (ref "U$11") (pin "3_WP") (pinfunction "WP_3_WP") (pintype "bidirectional"))
    )
    (net (code "84") (name "unconnected-(U$12-P$1-Pad1)") (class "Default")
      (node (ref "U$12") (pin "1") (pinfunction "P$1_1") (pintype "bidirectional"))
    )
    (net (code "85") (name "unconnected-(U$12-P$2-Pad2)") (class "Default")
      (node (ref "U$12") (pin "2") (pinfunction "P$2_2") (pintype "bidirectional"))
    )
    (net (code "86") (name "unconnected-(U$13-P$1-Pad1)") (class "Default")
      (node (ref "U$13") (pin "1") (pinfunction "P$1_1") (pintype "bidirectional"))
    )
    (net (code "87") (name "unconnected-(U$13-P$2-Pad2)") (class "Default")
      (node (ref "U$13") (pin "2") (pinfunction "P$2_2") (pintype "bidirectional"))
    )
    (net (code "88") (name "unconnected-(U$14-P$1-Pad1)") (class "Default")
      (node (ref "U$14") (pin "1") (pinfunction "P$1_1") (pintype "bidirectional"))
    )
    (net (code "89") (name "unconnected-(U$14-P$2-Pad2)") (class "Default")
      (node (ref "U$14") (pin "2") (pinfunction "P$2_2") (pintype "bidirectional"))
    )
    (net (code "90") (name "unconnected-(U$15-P$1-Pad1)") (class "Default")
      (node (ref "U$15") (pin "1") (pinfunction "P$1_1") (pintype "bidirectional"))
    )
    (net (code "91") (name "unconnected-(U$15-P$2-Pad2)") (class "Default")
      (node (ref "U$15") (pin "2") (pinfunction "P$2_2") (pintype "bidirectional"))
    )
    (net (code "92") (name "unconnected-(U$16-P$1-Pad1)") (class "Default")
      (node (ref "U$16") (pin "1") (pinfunction "P$1_1") (pintype "bidirectional"))
    )
    (net (code "93") (name "unconnected-(U$16-P$2-Pad2)") (class "Default")
      (node (ref "U$16") (pin "2") (pinfunction "P$2_2") (pintype "bidirectional"))
    )
    (net (code "94") (name "unconnected-(U$17-P$1-Pad1)") (class "Default")
      (node (ref "U$17") (pin "1") (pinfunction "P$1_1") (pintype "bidirectional"))
    )
    (net (code "95") (name "unconnected-(U$17-P$2-Pad2)") (class "Default")
      (node (ref "U$17") (pin "2") (pinfunction "P$2_2") (pintype "bidirectional"))
    )
    (net (code "96") (name "unconnected-(U$19-P$1-Pad1)") (class "Default")
      (node (ref "U$19") (pin "1") (pinfunction "P$1_1") (pintype "bidirectional"))
    )
    (net (code "97") (name "unconnected-(U$19-P$2-Pad2)") (class "Default")
      (node (ref "U$19") (pin "2") (pinfunction "P$2_2") (pintype "bidirectional"))
    )
    (net (code "98") (name "unconnected-(U$20-P$1-Pad1)") (class "Default")
      (node (ref "U$20") (pin "1") (pinfunction "P$1_1") (pintype "bidirectional"))
    )
    (net (code "99") (name "unconnected-(U$20-P$2-Pad2)") (class "Default")
      (node (ref "U$20") (pin "2") (pinfunction "P$2_2") (pintype "bidirectional"))
    )
    (net (code "100") (name "unconnected-(U$25-P$1-Pad1)") (class "Default")
      (node (ref "U$25") (pin "1") (pinfunction "P$1_1") (pintype "bidirectional"))
    )
    (net (code "101") (name "unconnected-(U$25-P$2-Pad2)") (class "Default")
      (node (ref "U$25") (pin "2") (pinfunction "P$2_2") (pintype "bidirectional"))
    )
    (net (code "102") (name "unconnected-(U$26-P$1-Pad1)") (class "Default")
      (node (ref "U$26") (pin "1") (pinfunction "P$1_1") (pintype "bidirectional"))
    )
    (net (code "103") (name "unconnected-(U$26-P$2-Pad2)") (class "Default")
      (node (ref "U$26") (pin "2") (pinfunction "P$2_2") (pintype "bidirectional"))
    )
    (net (code "104") (name "unconnected-(USB-PadD+)") (class "Default")
      (node (ref "USB") (pin "D+") (pinfunction "D+_D+") (pintype "bidirectional"))
    )
    (net (code "105") (name "unconnected-(USB-PadD-)") (class "Default")
      (node (ref "USB") (pin "D-") (pinfunction "D-_D-") (pintype "bidirectional"))
    )
    (net (code "106") (name "unconnected-(USB-PadID)") (class "Default")
      (node (ref "USB") (pin "ID") (pinfunction "ID_ID") (pintype "bidirectional"))
    )
  )
)
